# psu.net
KiCad netlist of a schematic drawn in EAGLE
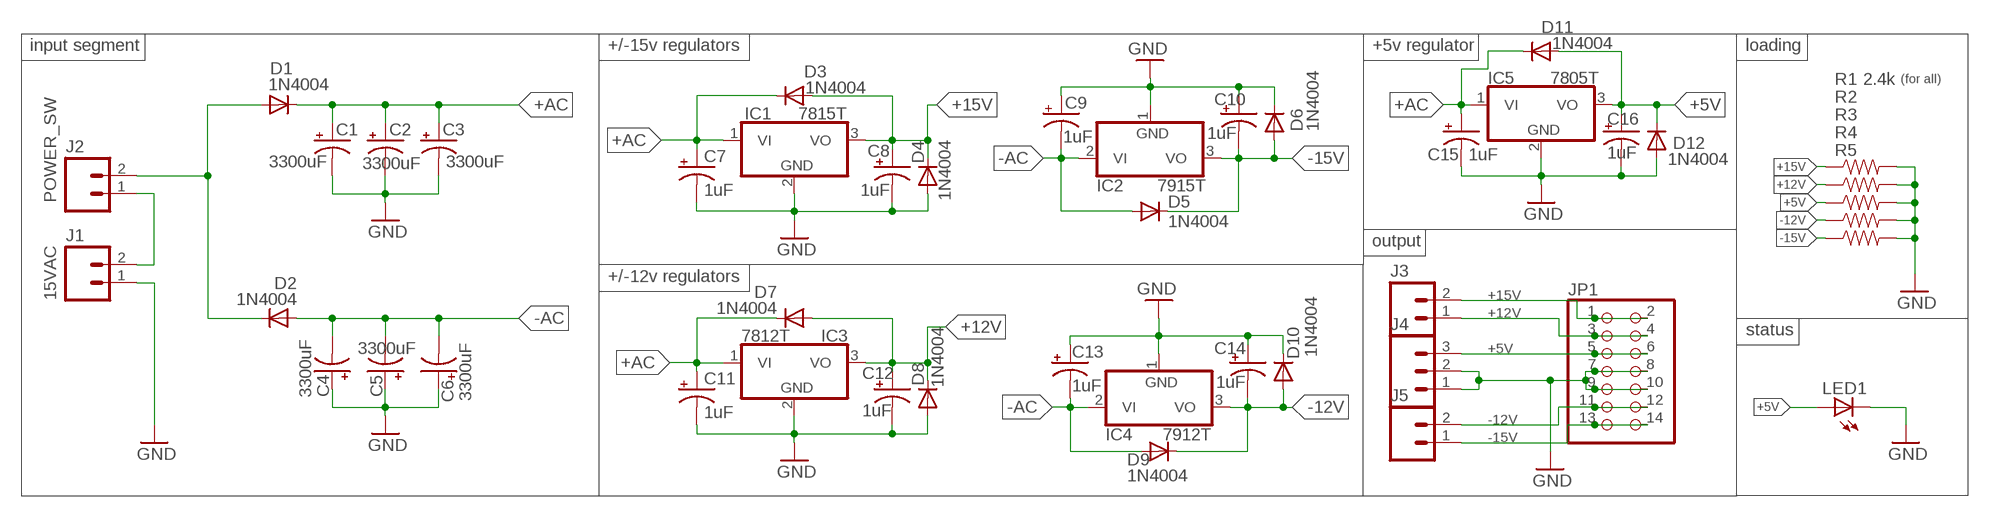
[diagram p0: schematic, sheet 1]

(export (version "E")
  (design (tool "Eeschema 10.0.6"))
  (components
    (comp (ref "C1")
      (value "3300uF")
      (footprint "eagle-import:E7,5-18")
      (libsource (lib "eagle-import") (part "CPOL-USE7.5-18"))
    )
    (comp (ref "C2")
      (value "3300uF")
      (footprint "eagle-import:E7,5-18")
      (libsource (lib "eagle-import") (part "CPOL-USE7.5-18"))
    )
    (comp (ref "C3")
      (value "3300uF")
      (footprint "eagle-import:E7,5-18")
      (libsource (lib "eagle-import") (part "CPOL-USE7.5-18"))
    )
    (comp (ref "C4")
      (value "3300uF")
      (footprint "eagle-import:E7,5-18")
      (libsource (lib "eagle-import") (part "CPOL-USE7.5-18"))
    )
    (comp (ref "C5")
      (value "3300uF")
      (footprint "eagle-import:E7,5-18")
      (libsource (lib "eagle-import") (part "CPOL-USE7.5-18"))
    )
    (comp (ref "C6")
      (value "3300uF")
      (footprint "eagle-import:E7,5-18")
      (libsource (lib "eagle-import") (part "CPOL-USE7.5-18"))
    )
    (comp (ref "C7")
      (value "1uF")
      (footprint "eagle-import:E2,5-5")
      (libsource (lib "eagle-import") (part "CPOL-USE2.5-5"))
    )
    (comp (ref "C8")
      (value "1uF")
      (footprint "eagle-import:E2,5-5")
      (libsource (lib "eagle-import") (part "CPOL-USE2.5-5"))
    )
    (comp (ref "C9")
      (value "1uF")
      (footprint "eagle-import:E2,5-5")
      (libsource (lib "eagle-import") (part "CPOL-USE2.5-5"))
    )
    (comp (ref "C10")
      (value "1uF")
      (footprint "eagle-import:E2,5-5")
      (libsource (lib "eagle-import") (part "CPOL-USE2.5-5"))
    )
    (comp (ref "C11")
      (value "1uF")
      (footprint "eagle-import:E2,5-5")
      (libsource (lib "eagle-import") (part "CPOL-USE2.5-5"))
    )
    (comp (ref "C12")
      (value "1uF")
      (footprint "eagle-import:E2,5-5")
      (libsource (lib "eagle-import") (part "CPOL-USE2.5-5"))
    )
    (comp (ref "C13")
      (value "1uF")
      (footprint "eagle-import:E2,5-5")
      (libsource (lib "eagle-import") (part "CPOL-USE2.5-5"))
    )
    (comp (ref "C14")
      (value "1uF")
      (footprint "eagle-import:E2,5-5")
      (libsource (lib "eagle-import") (part "CPOL-USE2.5-5"))
    )
    (comp (ref "C15")
      (value "1uF")
      (footprint "eagle-import:E2,5-5")
      (libsource (lib "eagle-import") (part "CPOL-USE2.5-5"))
    )
    (comp (ref "C16")
      (value "1uF")
      (footprint "eagle-import:E2,5-5")
      (libsource (lib "eagle-import") (part "CPOL-USE2.5-5"))
    )
    (comp (ref "D1")
      (value "1N4004")
      (footprint "eagle-import:DO41-10")
      (libsource (lib "eagle-import") (part "1N4004"))
    )
    (comp (ref "D2")
      (value "1N4004")
      (footprint "eagle-import:DO41-10")
      (libsource (lib "eagle-import") (part "1N4004"))
    )
    (comp (ref "D3")
      (value "1N4004")
      (footprint "eagle-import:DO41-10")
      (libsource (lib "eagle-import") (part "1N4004"))
    )
    (comp (ref "D4")
      (value "1N4004")
      (footprint "eagle-import:DO41-10")
      (libsource (lib "eagle-import") (part "1N4004"))
    )
    (comp (ref "D5")
      (value "1N4004")
      (footprint "eagle-import:DO41-10")
      (libsource (lib "eagle-import") (part "1N4004"))
    )
    (comp (ref "D6")
      (value "1N4004")
      (footprint "eagle-import:DO41-10")
      (libsource (lib "eagle-import") (part "1N4004"))
    )
    (comp (ref "D7")
      (value "1N4004")
      (footprint "eagle-import:DO41-10")
      (libsource (lib "eagle-import") (part "1N4004"))
    )
    (comp (ref "D8")
      (value "1N4004")
      (footprint "eagle-import:DO41-10")
      (libsource (lib "eagle-import") (part "1N4004"))
    )
    (comp (ref "D9")
      (value "1N4004")
      (footprint "eagle-import:DO41-10")
      (libsource (lib "eagle-import") (part "1N4004"))
    )
    (comp (ref "D10")
      (value "1N4004")
      (footprint "eagle-import:DO41-10")
      (libsource (lib "eagle-import") (part "1N4004"))
    )
    (comp (ref "D11")
      (value "1N4004")
      (footprint "eagle-import:DO41-10")
      (libsource (lib "eagle-import") (part "1N4004"))
    )
    (comp (ref "D12")
      (value "1N4004")
      (footprint "eagle-import:DO41-10")
      (libsource (lib "eagle-import") (part "1N4004"))
    )
    (comp (ref "IC1")
      (value "7815T")
      (footprint "eagle-import:TO220H")
      (libsource (lib "eagle-import") (part "78T15"))
    )
    (comp (ref "IC2")
      (value "7915T")
      (footprint "eagle-import:TO220H")
      (libsource (lib "eagle-import") (part "79T15"))
    )
    (comp (ref "IC3")
      (value "7812T")
      (footprint "eagle-import:TO220H")
      (libsource (lib "eagle-import") (part "78T12"))
    )
    (comp (ref "IC4")
      (value "7912T")
      (footprint "eagle-import:TO220H")
      (libsource (lib "eagle-import") (part "79T12"))
    )
    (comp (ref "IC5")
      (value "7805T")
      (footprint "eagle-import:TO220H")
      (libsource (lib "eagle-import") (part "78T05"))
    )
    (comp (ref "J1")
      (value "15VAC")
      (footprint "eagle-import:SCREWTERMINAL-5MM-2")
      (libsource (lib "eagle-import") (part "M025MM"))
    )
    (comp (ref "J2")
      (value "POWER_SW")
      (footprint "eagle-import:SCREWTERMINAL-5MM-2")
      (libsource (lib "eagle-import") (part "M025MM"))
    )
    (comp (ref "J3")
      (value "M025MM")
      (footprint "eagle-import:SCREWTERMINAL-5MM-2")
      (libsource (lib "eagle-import") (part "M025MM"))
    )
    (comp (ref "J4")
      (value "M03-SCREW-5MM")
      (footprint "eagle-import:SCREWTERMINAL-5MM-3")
      (libsource (lib "eagle-import") (part "M03-SCREW-5MM"))
    )
    (comp (ref "J5")
      (value "M025MM")
      (footprint "eagle-import:SCREWTERMINAL-5MM-2")
      (libsource (lib "eagle-import") (part "M025MM"))
    )
    (comp (ref "JP1")
      (value "PINHD-2X7")
      (footprint "eagle-import:2X07")
      (libsource (lib "eagle-import") (part "PINHD-2X7"))
    )
    (comp (ref "LED1")
      (value "LED3MM")
      (footprint "eagle-import:LED3MM")
      (libsource (lib "eagle-import") (part "LED3MM"))
    )
    (comp (ref "R1")
      (value "2.4k")
      (footprint "eagle-import:0805")
      (libsource (lib "eagle-import") (part "RESISTOR0805-RES"))
    )
    (comp (ref "R2")
      (value "2.4k")
      (footprint "eagle-import:0805")
      (libsource (lib "eagle-import") (part "RESISTOR0805-RES"))
    )
    (comp (ref "R3")
      (value "2.4k")
      (footprint "eagle-import:0805")
      (libsource (lib "eagle-import") (part "RESISTOR0805-RES"))
    )
    (comp (ref "R4")
      (value "2.4k")
      (footprint "eagle-import:0805")
      (libsource (lib "eagle-import") (part "RESISTOR0805-RES"))
    )
    (comp (ref "R5")
      (value "2.4k")
      (footprint "eagle-import:0805")
      (libsource (lib "eagle-import") (part "RESISTOR0805-RES"))
    )
  )
  (nets
    (net (code "1") (name "+5V") (class "Default")
      (node (ref "C16") (pin "+") (pinfunction "+_+") (pintype "passive"))
      (node (ref "D11") (pin "A") (pinfunction "A_A") (pintype "passive"))
      (node (ref "D12") (pin "C") (pinfunction "C_C") (pintype "passive"))
      (node (ref "IC5") (pin "3") (pinfunction "VO_3") (pintype "passive"))
      (node (ref "J4") (pin "3") (pinfunction "3_3") (pintype "passive"))
      (node (ref "JP1") (pin "5") (pinfunction "5_5") (pintype "passive"))
      (node (ref "JP1") (pin "6") (pinfunction "6_6") (pintype "passive"))
      (node (ref "LED1") (pin "A") (pinfunction "A_A") (pintype "passive"))
      (node (ref "R3") (pin "1") (pinfunction "1_1") (pintype "passive"))
    )
    (net (code "2") (name "+12V") (class "Default")
      (node (ref "C12") (pin "+") (pinfunction "+_+") (pintype "passive"))
      (node (ref "D7") (pin "A") (pinfunction "A_A") (pintype "passive"))
      (node (ref "D8") (pin "C") (pinfunction "C_C") (pintype "passive"))
      (node (ref "IC3") (pin "3") (pinfunction "VO_3") (pintype "passive"))
      (node (ref "J3") (pin "1") (pinfunction "1_1") (pintype "passive"))
      (node (ref "JP1") (pin "3") (pinfunction "3_3") (pintype "passive"))
      (node (ref "JP1") (pin "4") (pinfunction "4_4") (pintype "passive"))
      (node (ref "R2") (pin "1") (pinfunction "1_1") (pintype "passive"))
    )
    (net (code "3") (name "+15V") (class "Default")
      (node (ref "C8") (pin "+") (pinfunction "+_+") (pintype "passive"))
      (node (ref "D3") (pin "A") (pinfunction "A_A") (pintype "passive"))
      (node (ref "D4") (pin "C") (pinfunction "C_C") (pintype "passive"))
      (node (ref "IC1") (pin "3") (pinfunction "VO_3") (pintype "passive"))
      (node (ref "J3") (pin "2") (pinfunction "2_2") (pintype "passive"))
      (node (ref "JP1") (pin "1") (pinfunction "1_1") (pintype "passive"))
      (node (ref "JP1") (pin "2") (pinfunction "2_2") (pintype "passive"))
      (node (ref "R1") (pin "1") (pinfunction "1_1") (pintype "passive"))
    )
    (net (code "4") (name "+AC") (class "Default")
      (node (ref "C1") (pin "+") (pinfunction "+_+") (pintype "passive"))
      (node (ref "C11") (pin "+") (pinfunction "+_+") (pintype "passive"))
      (node (ref "C15") (pin "+") (pinfunction "+_+") (pintype "passive"))
      (node (ref "C2") (pin "+") (pinfunction "+_+") (pintype "passive"))
      (node (ref "C3") (pin "+") (pinfunction "+_+") (pintype "passive"))
      (node (ref "C7") (pin "+") (pinfunction "+_+") (pintype "passive"))
      (node (ref "D1") (pin "C") (pinfunction "C_C") (pintype "passive"))
      (node (ref "D11") (pin "C") (pinfunction "C_C") (pintype "passive"))
      (node (ref "D3") (pin "C") (pinfunction "C_C") (pintype "passive"))
      (node (ref "D7") (pin "C") (pinfunction "C_C") (pintype "passive"))
      (node (ref "IC1") (pin "1") (pinfunction "VI_1") (pintype "input"))
      (node (ref "IC3") (pin "1") (pinfunction "VI_1") (pintype "input"))
      (node (ref "IC5") (pin "1") (pinfunction "VI_1") (pintype "input"))
    )
    (net (code "5") (name "-12V") (class "Default")
      (node (ref "C14") (pin "-") (pinfunction "-_-") (pintype "passive"))
      (node (ref "D10") (pin "A") (pinfunction "A_A") (pintype "passive"))
      (node (ref "D9") (pin "C") (pinfunction "C_C") (pintype "passive"))
      (node (ref "IC4") (pin "3") (pinfunction "VO_3") (pintype "passive"))
      (node (ref "J5") (pin "2") (pinfunction "2_2") (pintype "passive"))
      (node (ref "JP1") (pin "11") (pinfunction "11_11") (pintype "passive"))
      (node (ref "JP1") (pin "12") (pinfunction "12_12") (pintype "passive"))
      (node (ref "R4") (pin "1") (pinfunction "1_1") (pintype "passive"))
    )
    (net (code "6") (name "-15V") (class "Default")
      (node (ref "C10") (pin "-") (pinfunction "-_-") (pintype "passive"))
      (node (ref "D5") (pin "C") (pinfunction "C_C") (pintype "passive"))
      (node (ref "D6") (pin "A") (pinfunction "A_A") (pintype "passive"))
      (node (ref "IC2") (pin "3") (pinfunction "VO_3") (pintype "passive"))
      (node (ref "J5") (pin "1") (pinfunction "1_1") (pintype "passive"))
      (node (ref "JP1") (pin "13") (pinfunction "13_13") (pintype "passive"))
      (node (ref "JP1") (pin "14") (pinfunction "14_14") (pintype "passive"))
      (node (ref "R5") (pin "1") (pinfunction "1_1") (pintype "passive"))
    )
    (net (code "7") (name "-AC") (class "Default")
      (node (ref "C13") (pin "-") (pinfunction "-_-") (pintype "passive"))
      (node (ref "C4") (pin "-") (pinfunction "-_-") (pintype "passive"))
      (node (ref "C5") (pin "-") (pinfunction "-_-") (pintype "passive"))
      (node (ref "C6") (pin "-") (pinfunction "-_-") (pintype "passive"))
      (node (ref "C9") (pin "-") (pinfunction "-_-") (pintype "passive"))
      (node (ref "D2") (pin "A") (pinfunction "A_A") (pintype "passive"))
      (node (ref "D5") (pin "A") (pinfunction "A_A") (pintype "passive"))
      (node (ref "D9") (pin "A") (pinfunction "A_A") (pintype "passive"))
      (node (ref "IC2") (pin "2") (pinfunction "VI_2") (pintype "input"))
      (node (ref "IC4") (pin "2") (pinfunction "VI_2") (pintype "input"))
    )
    (net (code "8") (name "GND") (class "Default")
      (node (ref "C1") (pin "-") (pinfunction "-_-") (pintype "passive"))
      (node (ref "C10") (pin "+") (pinfunction "+_+") (pintype "passive"))
      (node (ref "C11") (pin "-") (pinfunction "-_-") (pintype "passive"))
      (node (ref "C12") (pin "-") (pinfunction "-_-") (pintype "passive"))
      (node (ref "C13") (pin "+") (pinfunction "+_+") (pintype "passive"))
      (node (ref "C14") (pin "+") (pinfunction "+_+") (pintype "passive"))
      (node (ref "C15") (pin "-") (pinfunction "-_-") (pintype "passive"))
      (node (ref "C16") (pin "-") (pinfunction "-_-") (pintype "passive"))
      (node (ref "C2") (pin "-") (pinfunction "-_-") (pintype "passive"))
      (node (ref "C3") (pin "-") (pinfunction "-_-") (pintype "passive"))
      (node (ref "C4") (pin "+") (pinfunction "+_+") (pintype "passive"))
      (node (ref "C5") (pin "+") (pinfunction "+_+") (pintype "passive"))
      (node (ref "C6") (pin "+") (pinfunction "+_+") (pintype "passive"))
      (node (ref "C7") (pin "-") (pinfunction "-_-") (pintype "passive"))
      (node (ref "C8") (pin "-") (pinfunction "-_-") (pintype "passive"))
      (node (ref "C9") (pin "+") (pinfunction "+_+") (pintype "passive"))
      (node (ref "D10") (pin "C") (pinfunction "C_C") (pintype "passive"))
      (node (ref "D12") (pin "A") (pinfunction "A_A") (pintype "passive"))
      (node (ref "D4") (pin "A") (pinfunction "A_A") (pintype "passive"))
      (node (ref "D6") (pin "C") (pinfunction "C_C") (pintype "passive"))
      (node (ref "D8") (pin "A") (pinfunction "A_A") (pintype "passive"))
      (node (ref "IC1") (pin "2") (pinfunction "GND_2") (pintype "passive"))
      (node (ref "IC2") (pin "1") (pinfunction "GND_1") (pintype "passive"))
      (node (ref "IC3") (pin "2") (pinfunction "GND_2") (pintype "passive"))
      (node (ref "IC4") (pin "1") (pinfunction "GND_1") (pintype "passive"))
      (node (ref "IC5") (pin "2") (pinfunction "GND_2") (pintype "passive"))
      (node (ref "J1") (pin "1") (pinfunction "1_1") (pintype "passive"))
      (node (ref "J4") (pin "1") (pinfunction "1_1") (pintype "passive"))
      (node (ref "J4") (pin "2") (pinfunction "2_2") (pintype "passive"))
      (node (ref "JP1") (pin "10") (pinfunction "10_10") (pintype "passive"))
      (node (ref "JP1") (pin "7") (pinfunction "7_7") (pintype "passive"))
      (node (ref "JP1") (pin "8") (pinfunction "8_8") (pintype "passive"))
      (node (ref "JP1") (pin "9") (pinfunction "9_9") (pintype "passive"))
      (node (ref "LED1") (pin "K") (pinfunction "C_K") (pintype "passive"))
      (node (ref "R1") (pin "2") (pinfunction "2_2") (pintype "passive"))
      (node (ref "R2") (pin "2") (pinfunction "2_2") (pintype "passive"))
      (node (ref "R3") (pin "2") (pinfunction "2_2") (pintype "passive"))
      (node (ref "R4") (pin "2") (pinfunction "2_2") (pintype "passive"))
      (node (ref "R5") (pin "2") (pinfunction "2_2") (pintype "passive"))
    )
    (net (code "9") (name "Net-(D1-PadA)") (class "Default")
      (node (ref "D1") (pin "A") (pinfunction "A_A") (pintype "passive"))
      (node (ref "D2") (pin "C") (pinfunction "C_C") (pintype "passive"))
      (node (ref "J2") (pin "2") (pinfunction "2_2") (pintype "passive"))
    )
    (net (code "10") (name "Net-(J1-Pad2)") (class "Default")
      (node (ref "J1") (pin "2") (pinfunction "2_2") (pintype "passive"))
      (node (ref "J2") (pin "1") (pinfunction "1_1") (pintype "passive"))
    )
  )
)
